# 20190213.net
KiCad netlist of a schematic drawn in EAGLE
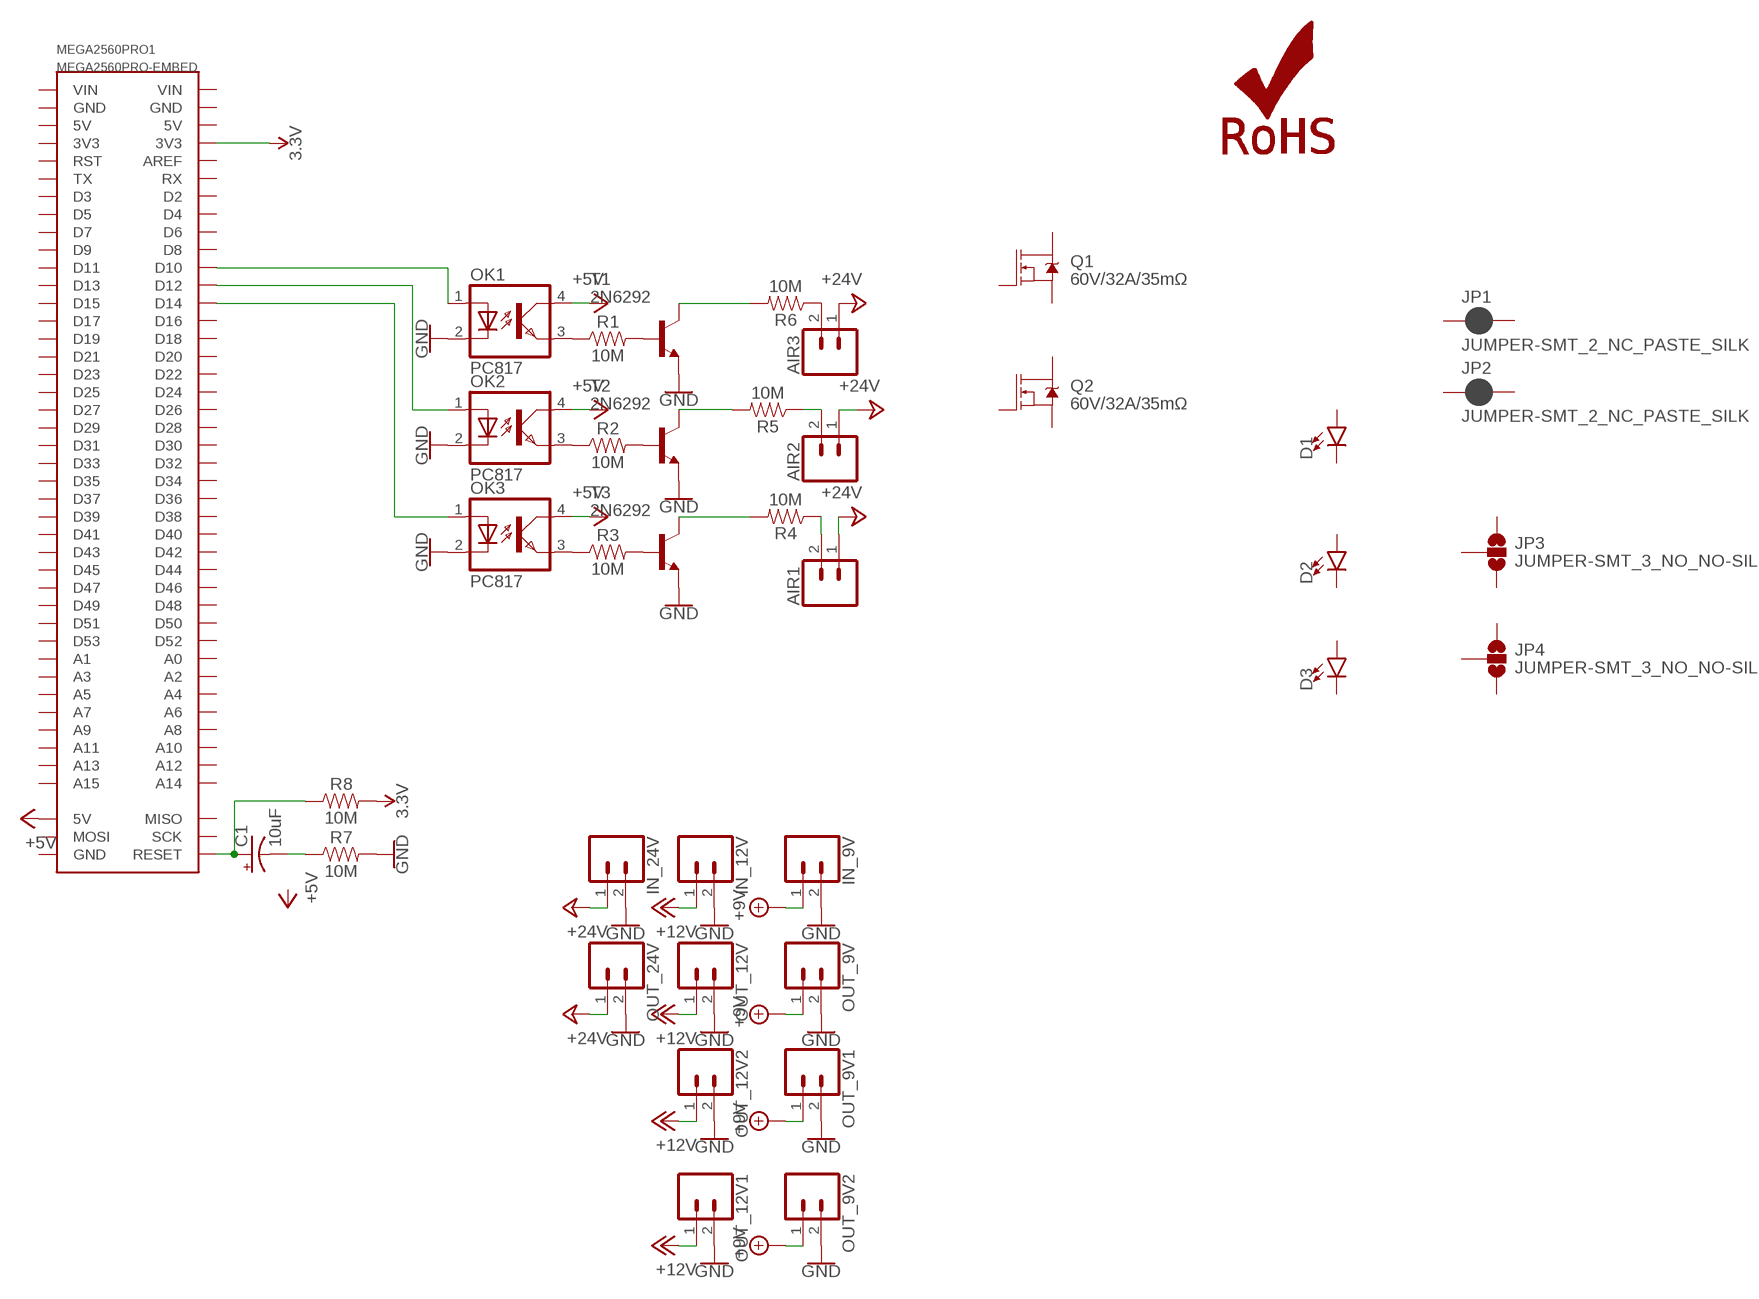
[diagram p0: schematic, sheet 1]

(export (version "E")
  (design (tool "Eeschema 10.0.6"))
  (components
    (comp (ref "AIR1")
      (value "CONN_02POLAR_LOCK")
      (footprint "eagle-import:MOLEX-1X2_LOCK")
      (libsource (lib "eagle-import") (part "CONN_02POLAR_LOCK"))
    )
    (comp (ref "AIR2")
      (value "CONN_02POLAR_LOCK")
      (footprint "eagle-import:MOLEX-1X2_LOCK")
      (libsource (lib "eagle-import") (part "CONN_02POLAR_LOCK"))
    )
    (comp (ref "AIR3")
      (value "CONN_02POLAR_LOCK")
      (footprint "eagle-import:MOLEX-1X2_LOCK")
      (libsource (lib "eagle-import") (part "CONN_02POLAR_LOCK"))
    )
    (comp (ref "C1")
      (value "10uF")
      (footprint "eagle-import:CPOL-RADIAL-2.5MM-5MM-KIT")
      (libsource (lib "eagle-import") (part "10UF-POLAR-RADIAL-2.5MM-KIT-25V-20%"))
    )
    (comp (ref "D1")
      (value "LED5MM")
      (footprint "eagle-import:LED_5MM")
      (libsource (lib "eagle-import") (part "LED5MM"))
    )
    (comp (ref "D2")
      (value "LED5MM")
      (footprint "eagle-import:LED_5MM")
      (libsource (lib "eagle-import") (part "LED5MM"))
    )
    (comp (ref "D3")
      (value "LED5MM")
      (footprint "eagle-import:LED_5MM")
      (libsource (lib "eagle-import") (part "LED5MM"))
    )
    (comp (ref "IN_9V")
      (value "CONN_02POLAR_LOCK")
      (footprint "eagle-import:MOLEX-1X2_LOCK")
      (libsource (lib "eagle-import") (part "CONN_02POLAR_LOCK"))
    )
    (comp (ref "IN_12V")
      (value "CONN_02POLAR_LOCK")
      (footprint "eagle-import:MOLEX-1X2_LOCK")
      (libsource (lib "eagle-import") (part "CONN_02POLAR_LOCK"))
    )
    (comp (ref "IN_24V")
      (value "CONN_02POLAR_LOCK")
      (footprint "eagle-import:MOLEX-1X2_LOCK")
      (libsource (lib "eagle-import") (part "CONN_02POLAR_LOCK"))
    )
    (comp (ref "JP1")
      (value "JUMPER-SMT_2_NC_PASTE_SILK")
      (footprint "eagle-import:SMT-JUMPER_2_NC_PASTE_SILK")
      (libsource (lib "eagle-import") (part "JUMPER-SMT_2_NC_PASTE_SILK"))
    )
    (comp (ref "JP2")
      (value "JUMPER-SMT_2_NC_PASTE_SILK")
      (footprint "eagle-import:SMT-JUMPER_2_NC_PASTE_SILK")
      (libsource (lib "eagle-import") (part "JUMPER-SMT_2_NC_PASTE_SILK"))
    )
    (comp (ref "JP3")
      (value "JUMPER-SMT_3_NO_NO-SILK")
      (footprint "eagle-import:SMT-JUMPER_3_NO_NO-SILK")
      (libsource (lib "eagle-import") (part "JUMPER-SMT_3_NO_NO-SILK"))
    )
    (comp (ref "JP4")
      (value "JUMPER-SMT_3_NO_NO-SILK")
      (footprint "eagle-import:SMT-JUMPER_3_NO_NO-SILK")
      (libsource (lib "eagle-import") (part "JUMPER-SMT_3_NO_NO-SILK"))
    )
    (comp (ref "LOGO1")
      (value "ROHS_LOGO")
      (footprint "eagle-import:ROHS_LOGO_0.18_IN")
      (libsource (lib "eagle-import") (part "ROHS_LOGO"))
    )
    (comp (ref "MEGA2560PRO1")
      (value "MEGA2560PRO-EMBED")
      (footprint "eagle-import:MEGA2560PRO-EMBED")
      (libsource (lib "eagle-import") (part "MEGA2560PRO-EMBED"))
    )
    (comp (ref "OK1")
      (value "PC817")
      (footprint "eagle-import:DIL04")
      (fields (field (name "MPN") "PC817X4J000F"))
      (libsource (lib "eagle-import") (part "PC817"))
    )
    (comp (ref "OK2")
      (value "PC817")
      (footprint "eagle-import:DIL04")
      (fields (field (name "MPN") "PC817X4J000F"))
      (libsource (lib "eagle-import") (part "PC817"))
    )
    (comp (ref "OK3")
      (value "PC817")
      (footprint "eagle-import:DIL04")
      (fields (field (name "MPN") "PC817X4J000F"))
      (libsource (lib "eagle-import") (part "PC817"))
    )
    (comp (ref "OUT_9V")
      (value "CONN_02POLAR_LOCK")
      (footprint "eagle-import:MOLEX-1X2_LOCK")
      (libsource (lib "eagle-import") (part "CONN_02POLAR_LOCK"))
    )
    (comp (ref "OUT_9V1")
      (value "CONN_02POLAR_LOCK")
      (footprint "eagle-import:MOLEX-1X2_LOCK")
      (libsource (lib "eagle-import") (part "CONN_02POLAR_LOCK"))
    )
    (comp (ref "OUT_9V2")
      (value "CONN_02POLAR_LOCK")
      (footprint "eagle-import:MOLEX-1X2_LOCK")
      (libsource (lib "eagle-import") (part "CONN_02POLAR_LOCK"))
    )
    (comp (ref "OUT_12V")
      (value "CONN_02POLAR_LOCK")
      (footprint "eagle-import:MOLEX-1X2_LOCK")
      (libsource (lib "eagle-import") (part "CONN_02POLAR_LOCK"))
    )
    (comp (ref "OUT_12V1")
      (value "CONN_02POLAR_LOCK")
      (footprint "eagle-import:MOLEX-1X2_LOCK")
      (libsource (lib "eagle-import") (part "CONN_02POLAR_LOCK"))
    )
    (comp (ref "OUT_12V2")
      (value "CONN_02POLAR_LOCK")
      (footprint "eagle-import:MOLEX-1X2_LOCK")
      (libsource (lib "eagle-import") (part "CONN_02POLAR_LOCK"))
    )
    (comp (ref "OUT_24V")
      (value "CONN_02POLAR_LOCK")
      (footprint "eagle-import:MOLEX-1X2_LOCK")
      (libsource (lib "eagle-import") (part "CONN_02POLAR_LOCK"))
    )
    (comp (ref "Q1")
      (value "60V/32A/35mΩ")
      (footprint "eagle-import:TO220V")
      (libsource (lib "eagle-import") (part "MOSFET-NCH-FQP30N06L"))
    )
    (comp (ref "Q2")
      (value "60V/32A/35mΩ")
      (footprint "eagle-import:TO220V")
      (libsource (lib "eagle-import") (part "MOSFET-NCH-FQP30N06L"))
    )
    (comp (ref "R1")
      (value "10M")
      (footprint "eagle-import:AXIAL-0.3")
      (libsource (lib "eagle-import") (part "10MOHM-HORIZ-1/4W-5%"))
    )
    (comp (ref "R2")
      (value "10M")
      (footprint "eagle-import:AXIAL-0.3")
      (libsource (lib "eagle-import") (part "10MOHM-HORIZ-1/4W-5%"))
    )
    (comp (ref "R3")
      (value "10M")
      (footprint "eagle-import:AXIAL-0.3")
      (libsource (lib "eagle-import") (part "10MOHM-HORIZ-1/4W-5%"))
    )
    (comp (ref "R4")
      (value "10M")
      (footprint "eagle-import:AXIAL-0.3")
      (libsource (lib "eagle-import") (part "10MOHM-HORIZ-1/4W-5%"))
    )
    (comp (ref "R5")
      (value "10M")
      (footprint "eagle-import:AXIAL-0.3")
      (libsource (lib "eagle-import") (part "10MOHM-HORIZ-1/4W-5%"))
    )
    (comp (ref "R6")
      (value "10M")
      (footprint "eagle-import:AXIAL-0.3")
      (libsource (lib "eagle-import") (part "10MOHM-HORIZ-1/4W-5%"))
    )
    (comp (ref "R7")
      (value "10M")
      (footprint "eagle-import:AXIAL-0.3")
      (libsource (lib "eagle-import") (part "10MOHM-HORIZ-1/4W-5%"))
    )
    (comp (ref "R8")
      (value "10M")
      (footprint "eagle-import:AXIAL-0.3")
      (libsource (lib "eagle-import") (part "10MOHM-HORIZ-1/4W-5%"))
    )
    (comp (ref "T1")
      (value "2N6292")
      (footprint "eagle-import:TO220")
      (libsource (lib "eagle-import") (part "2N6292"))
    )
    (comp (ref "T2")
      (value "2N6292")
      (footprint "eagle-import:TO220")
      (libsource (lib "eagle-import") (part "2N6292"))
    )
    (comp (ref "T3")
      (value "2N6292")
      (footprint "eagle-import:TO220")
      (libsource (lib "eagle-import") (part "2N6292"))
    )
  )
  (nets
    (net (code "1") (name "+5V") (class "Default")
      (node (ref "MEGA2560PRO1") (pin "5V@3") (pinfunction "5V_5V@3") (pintype "bidirectional"))
      (node (ref "OK1") (pin "4") (pinfunction "COL_4") (pintype "passive"))
      (node (ref "OK2") (pin "4") (pinfunction "COL_4") (pintype "passive"))
      (node (ref "OK3") (pin "4") (pinfunction "COL_4") (pintype "passive"))
    )
    (net (code "2") (name "+9V") (class "Default")
      (node (ref "IN_9V") (pin "1") (pinfunction "1_1") (pintype "passive"))
      (node (ref "OUT_9V") (pin "1") (pinfunction "1_1") (pintype "passive"))
      (node (ref "OUT_9V1") (pin "1") (pinfunction "1_1") (pintype "passive"))
      (node (ref "OUT_9V2") (pin "1") (pinfunction "1_1") (pintype "passive"))
    )
    (net (code "3") (name "+12V") (class "Default")
      (node (ref "IN_12V") (pin "1") (pinfunction "1_1") (pintype "passive"))
      (node (ref "OUT_12V") (pin "1") (pinfunction "1_1") (pintype "passive"))
      (node (ref "OUT_12V1") (pin "1") (pinfunction "1_1") (pintype "passive"))
      (node (ref "OUT_12V2") (pin "1") (pinfunction "1_1") (pintype "passive"))
    )
    (net (code "4") (name "+24V") (class "Default")
      (node (ref "AIR1") (pin "1") (pinfunction "1_1") (pintype "passive"))
      (node (ref "AIR2") (pin "1") (pinfunction "1_1") (pintype "passive"))
      (node (ref "AIR3") (pin "1") (pinfunction "1_1") (pintype "passive"))
      (node (ref "IN_24V") (pin "1") (pinfunction "1_1") (pintype "passive"))
      (node (ref "OUT_24V") (pin "1") (pinfunction "1_1") (pintype "passive"))
    )
    (net (code "5") (name "3.3V") (class "Default")
      (node (ref "MEGA2560PRO1") (pin "3V3@2") (pinfunction "3V3_3V3@2") (pintype "bidirectional"))
      (node (ref "R8") (pin "P$2") (pinfunction "2_P$2") (pintype "passive"))
    )
    (net (code "6") (name "GND") (class "Default")
      (node (ref "IN_12V") (pin "2") (pinfunction "2_2") (pintype "passive"))
      (node (ref "IN_24V") (pin "2") (pinfunction "2_2") (pintype "passive"))
      (node (ref "IN_9V") (pin "2") (pinfunction "2_2") (pintype "passive"))
      (node (ref "OK1") (pin "2") (pinfunction "C_2") (pintype "passive"))
      (node (ref "OK2") (pin "2") (pinfunction "C_2") (pintype "passive"))
      (node (ref "OK3") (pin "2") (pinfunction "C_2") (pintype "passive"))
      (node (ref "OUT_12V") (pin "2") (pinfunction "2_2") (pintype "passive"))
      (node (ref "OUT_12V1") (pin "2") (pinfunction "2_2") (pintype "passive"))
      (node (ref "OUT_12V2") (pin "2") (pinfunction "2_2") (pintype "passive"))
      (node (ref "OUT_24V") (pin "2") (pinfunction "2_2") (pintype "passive"))
      (node (ref "OUT_9V") (pin "2") (pinfunction "2_2") (pintype "passive"))
      (node (ref "OUT_9V1") (pin "2") (pinfunction "2_2") (pintype "passive"))
      (node (ref "OUT_9V2") (pin "2") (pinfunction "2_2") (pintype "passive"))
      (node (ref "R7") (pin "P$2") (pinfunction "2_P$2") (pintype "passive"))
      (node (ref "T1") (pin "3") (pinfunction "E_3") (pintype "passive"))
      (node (ref "T2") (pin "3") (pinfunction "E_3") (pintype "passive"))
      (node (ref "T3") (pin "3") (pinfunction "E_3") (pintype "passive"))
    )
    (net (code "7") (name "Net-(C1-+)") (class "Default")
      (node (ref "C1") (pin "1") (pinfunction "+_1") (pintype "passive"))
      (node (ref "MEGA2560PRO1") (pin "RESET") (pinfunction "RESET_RESET") (pintype "bidirectional"))
      (node (ref "R8") (pin "P$1") (pinfunction "1_P$1") (pintype "passive"))
    )
    (net (code "8") (name "Net-(C1--)") (class "Default")
      (node (ref "C1") (pin "2") (pinfunction "-_2") (pintype "passive"))
      (node (ref "R7") (pin "P$1") (pinfunction "1_P$1") (pintype "passive"))
    )
    (net (code "9") (name "Net-(OK1-A)") (class "Default")
      (node (ref "MEGA2560PRO1") (pin "D10") (pinfunction "D10_D10") (pintype "bidirectional"))
      (node (ref "OK1") (pin "1") (pinfunction "A_1") (pintype "passive"))
    )
    (net (code "10") (name "Net-(OK1-EMIT)") (class "Default")
      (node (ref "OK1") (pin "3") (pinfunction "EMIT_3") (pintype "passive"))
      (node (ref "R1") (pin "P$1") (pinfunction "1_P$1") (pintype "passive"))
    )
    (net (code "11") (name "Net-(OK2-A)") (class "Default")
      (node (ref "MEGA2560PRO1") (pin "D12") (pinfunction "D12_D12") (pintype "bidirectional"))
      (node (ref "OK2") (pin "1") (pinfunction "A_1") (pintype "passive"))
    )
    (net (code "12") (name "Net-(OK2-EMIT)") (class "Default")
      (node (ref "OK2") (pin "3") (pinfunction "EMIT_3") (pintype "passive"))
      (node (ref "R2") (pin "P$1") (pinfunction "1_P$1") (pintype "passive"))
    )
    (net (code "13") (name "Net-(OK3-A)") (class "Default")
      (node (ref "MEGA2560PRO1") (pin "D14") (pinfunction "D14_D14") (pintype "bidirectional"))
      (node (ref "OK3") (pin "1") (pinfunction "A_1") (pintype "passive"))
    )
    (net (code "14") (name "Net-(OK3-EMIT)") (class "Default")
      (node (ref "OK3") (pin "3") (pinfunction "EMIT_3") (pintype "passive"))
      (node (ref "R3") (pin "P$1") (pinfunction "1_P$1") (pintype "passive"))
    )
    (net (code "15") (name "Net-(R1-2)") (class "Default")
      (node (ref "R1") (pin "P$2") (pinfunction "2_P$2") (pintype "passive"))
      (node (ref "T1") (pin "1") (pinfunction "B_1") (pintype "passive"))
    )
    (net (code "16") (name "Net-(R2-2)") (class "Default")
      (node (ref "R2") (pin "P$2") (pinfunction "2_P$2") (pintype "passive"))
      (node (ref "T2") (pin "1") (pinfunction "B_1") (pintype "passive"))
    )
    (net (code "17") (name "Net-(R3-2)") (class "Default")
      (node (ref "R3") (pin "P$2") (pinfunction "2_P$2") (pintype "passive"))
      (node (ref "T3") (pin "1") (pinfunction "B_1") (pintype "passive"))
    )
    (net (code "18") (name "Net-(R4-1)") (class "Default")
      (node (ref "AIR1") (pin "2") (pinfunction "2_2") (pintype "passive"))
      (node (ref "R4") (pin "P$1") (pinfunction "1_P$1") (pintype "passive"))
    )
    (net (code "19") (name "Net-(R4-2)") (class "Default")
      (node (ref "R4") (pin "P$2") (pinfunction "2_P$2") (pintype "passive"))
      (node (ref "T3") (pin "2") (pinfunction "C_2") (pintype "passive"))
    )
    (net (code "20") (name "Net-(R5-1)") (class "Default")
      (node (ref "AIR2") (pin "2") (pinfunction "2_2") (pintype "passive"))
      (node (ref "R5") (pin "P$1") (pinfunction "1_P$1") (pintype "passive"))
    )
    (net (code "21") (name "Net-(R5-2)") (class "Default")
      (node (ref "R5") (pin "P$2") (pinfunction "2_P$2") (pintype "passive"))
      (node (ref "T2") (pin "2") (pinfunction "C_2") (pintype "passive"))
    )
    (net (code "22") (name "Net-(R6-1)") (class "Default")
      (node (ref "AIR3") (pin "2") (pinfunction "2_2") (pintype "passive"))
      (node (ref "R6") (pin "P$1") (pinfunction "1_P$1") (pintype "passive"))
    )
    (net (code "23") (name "Net-(R6-2)") (class "Default")
      (node (ref "R6") (pin "P$2") (pinfunction "2_P$2") (pintype "passive"))
      (node (ref "T1") (pin "2") (pinfunction "C_2") (pintype "passive"))
    )
    (net (code "24") (name "unconnected-(D1-C-PadK)") (class "Default")
      (node (ref "D1") (pin "K") (pinfunction "C_K") (pintype "passive"))
    )
    (net (code "25") (name "unconnected-(D1-PadA)") (class "Default")
      (node (ref "D1") (pin "A") (pinfunction "A_A") (pintype "passive"))
    )
    (net (code "26") (name "unconnected-(D2-C-PadK)") (class "Default")
      (node (ref "D2") (pin "K") (pinfunction "C_K") (pintype "passive"))
    )
    (net (code "27") (name "unconnected-(D2-PadA)") (class "Default")
      (node (ref "D2") (pin "A") (pinfunction "A_A") (pintype "passive"))
    )
    (net (code "28") (name "unconnected-(D3-C-PadK)") (class "Default")
      (node (ref "D3") (pin "K") (pinfunction "C_K") (pintype "passive"))
    )
    (net (code "29") (name "unconnected-(D3-PadA)") (class "Default")
      (node (ref "D3") (pin "A") (pinfunction "A_A") (pintype "passive"))
    )
    (net (code "30") (name "unconnected-(JP1-Pad1)") (class "Default")
      (node (ref "JP1") (pin "1") (pinfunction "1_1") (pintype "passive"))
    )
    (net (code "31") (name "unconnected-(JP1-Pad2)") (class "Default")
      (node (ref "JP1") (pin "2") (pinfunction "2_2") (pintype "passive"))
    )
    (net (code "32") (name "unconnected-(JP2-Pad1)") (class "Default")
      (node (ref "JP2") (pin "1") (pinfunction "1_1") (pintype "passive"))
    )
    (net (code "33") (name "unconnected-(JP2-Pad2)") (class "Default")
      (node (ref "JP2") (pin "2") (pinfunction "2_2") (pintype "passive"))
    )
    (net (code "34") (name "unconnected-(JP3-Pad1)") (class "Default")
      (node (ref "JP3") (pin "1") (pinfunction "1_1") (pintype "passive"))
    )
    (net (code "35") (name "unconnected-(JP3-Pad2)") (class "Default")
      (node (ref "JP3") (pin "2") (pinfunction "2_2") (pintype "passive"))
    )
    (net (code "36") (name "unconnected-(JP3-Pad3)") (class "Default")
      (node (ref "JP3") (pin "3") (pinfunction "3_3") (pintype "passive"))
    )
    (net (code "37") (name "unconnected-(JP4-Pad1)") (class "Default")
      (node (ref "JP4") (pin "1") (pinfunction "1_1") (pintype "passive"))
    )
    (net (code "38") (name "unconnected-(JP4-Pad2)") (class "Default")
      (node (ref "JP4") (pin "2") (pinfunction "2_2") (pintype "passive"))
    )
    (net (code "39") (name "unconnected-(JP4-Pad3)") (class "Default")
      (node (ref "JP4") (pin "3") (pinfunction "3_3") (pintype "passive"))
    )
    (net (code "40") (name "unconnected-(MEGA2560PRO1-3V3-Pad3V3@1)") (class "Default")
      (node (ref "MEGA2560PRO1") (pin "3V3@1") (pinfunction "3V3_3V3@1") (pintype "bidirectional"))
    )
    (net (code "41") (name "unconnected-(MEGA2560PRO1-5V-Pad5V@1)") (class "Default")
      (node (ref "MEGA2560PRO1") (pin "5V@1") (pinfunction "5V_5V@1") (pintype "bidirectional"))
    )
    (net (code "42") (name "unconnected-(MEGA2560PRO1-5V-Pad5V@2)") (class "Default")
      (node (ref "MEGA2560PRO1") (pin "5V@2") (pinfunction "5V_5V@2") (pintype "bidirectional"))
    )
    (net (code "43") (name "unconnected-(MEGA2560PRO1-GND-PadGND@1)") (class "Default")
      (node (ref "MEGA2560PRO1") (pin "GND@1") (pinfunction "GND_GND@1") (pintype "bidirectional"))
    )
    (net (code "44") (name "unconnected-(MEGA2560PRO1-GND-PadGND@2)") (class "Default")
      (node (ref "MEGA2560PRO1") (pin "GND@2") (pinfunction "GND_GND@2") (pintype "bidirectional"))
    )
    (net (code "45") (name "unconnected-(MEGA2560PRO1-GND-PadGND@3)") (class "Default")
      (node (ref "MEGA2560PRO1") (pin "GND@3") (pinfunction "GND_GND@3") (pintype "bidirectional"))
    )
    (net (code "46") (name "unconnected-(MEGA2560PRO1-PadA0)") (class "Default")
      (node (ref "MEGA2560PRO1") (pin "A0") (pinfunction "A0_A0") (pintype "bidirectional"))
    )
    (net (code "47") (name "unconnected-(MEGA2560PRO1-PadA1)") (class "Default")
      (node (ref "MEGA2560PRO1") (pin "A1") (pinfunction "A1_A1") (pintype "bidirectional"))
    )
    (net (code "48") (name "unconnected-(MEGA2560PRO1-PadA2)") (class "Default")
      (node (ref "MEGA2560PRO1") (pin "A2") (pinfunction "A2_A2") (pintype "bidirectional"))
    )
    (net (code "49") (name "unconnected-(MEGA2560PRO1-PadA3)") (class "Default")
      (node (ref "MEGA2560PRO1") (pin "A3") (pinfunction "A3_A3") (pintype "bidirectional"))
    )
    (net (code "50") (name "unconnected-(MEGA2560PRO1-PadA4)") (class "Default")
      (node (ref "MEGA2560PRO1") (pin "A4") (pinfunction "A4_A4") (pintype "bidirectional"))
    )
    (net (code "51") (name "unconnected-(MEGA2560PRO1-PadA5)") (class "Default")
      (node (ref "MEGA2560PRO1") (pin "A5") (pinfunction "A5_A5") (pintype "bidirectional"))
    )
    (net (code "52") (name "unconnected-(MEGA2560PRO1-PadA6)") (class "Default")
      (node (ref "MEGA2560PRO1") (pin "A6") (pinfunction "A6_A6") (pintype "bidirectional"))
    )
    (net (code "53") (name "unconnected-(MEGA2560PRO1-PadA7)") (class "Default")
      (node (ref "MEGA2560PRO1") (pin "A7") (pinfunction "A7_A7") (pintype "bidirectional"))
    )
    (net (code "54") (name "unconnected-(MEGA2560PRO1-PadA8)") (class "Default")
      (node (ref "MEGA2560PRO1") (pin "A8") (pinfunction "A8_A8") (pintype "bidirectional"))
    )
    (net (code "55") (name "unconnected-(MEGA2560PRO1-PadA9)") (class "Default")
      (node (ref "MEGA2560PRO1") (pin "A9") (pinfunction "A9_A9") (pintype "bidirectional"))
    )
    (net (code "56") (name "unconnected-(MEGA2560PRO1-PadA10)") (class "Default")
      (node (ref "MEGA2560PRO1") (pin "A10") (pinfunction "A10_A10") (pintype "bidirectional"))
    )
    (net (code "57") (name "unconnected-(MEGA2560PRO1-PadA11)") (class "Default")
      (node (ref "MEGA2560PRO1") (pin "A11") (pinfunction "A11_A11") (pintype "bidirectional"))
    )
    (net (code "58") (name "unconnected-(MEGA2560PRO1-PadA12)") (class "Default")
      (node (ref "MEGA2560PRO1") (pin "A12") (pinfunction "A12_A12") (pintype "bidirectional"))
    )
    (net (code "59") (name "unconnected-(MEGA2560PRO1-PadA13)") (class "Default")
      (node (ref "MEGA2560PRO1") (pin "A13") (pinfunction "A13_A13") (pintype "bidirectional"))
    )
    (net (code "60") (name "unconnected-(MEGA2560PRO1-PadA14)") (class "Default")
      (node (ref "MEGA2560PRO1") (pin "A14") (pinfunction "A14_A14") (pintype "bidirectional"))
    )
    (net (code "61") (name "unconnected-(MEGA2560PRO1-PadA15)") (class "Default")
      (node (ref "MEGA2560PRO1") (pin "A15") (pinfunction "A15_A15") (pintype "bidirectional"))
    )
    (net (code "62") (name "unconnected-(MEGA2560PRO1-PadAREF)") (class "Default")
      (node (ref "MEGA2560PRO1") (pin "AREF") (pinfunction "AREF_AREF") (pintype "bidirectional"))
    )
    (net (code "63") (name "unconnected-(MEGA2560PRO1-PadD2)") (class "Default")
      (node (ref "MEGA2560PRO1") (pin "D2") (pinfunction "D2_D2") (pintype "bidirectional"))
    )
    (net (code "64") (name "unconnected-(MEGA2560PRO1-PadD3)") (class "Default")
      (node (ref "MEGA2560PRO1") (pin "D3") (pinfunction "D3_D3") (pintype "bidirectional"))
    )
    (net (code "65") (name "unconnected-(MEGA2560PRO1-PadD4)") (class "Default")
      (node (ref "MEGA2560PRO1") (pin "D4") (pinfunction "D4_D4") (pintype "bidirectional"))
    )
    (net (code "66") (name "unconnected-(MEGA2560PRO1-PadD5)") (class "Default")
      (node (ref "MEGA2560PRO1") (pin "D5") (pinfunction "D5_D5") (pintype "bidirectional"))
    )
    (net (code "67") (name "unconnected-(MEGA2560PRO1-PadD6)") (class "Default")
      (node (ref "MEGA2560PRO1") (pin "D6") (pinfunction "D6_D6") (pintype "bidirectional"))
    )
    (net (code "68") (name "unconnected-(MEGA2560PRO1-PadD7)") (class "Default")
      (node (ref "MEGA2560PRO1") (pin "D7") (pinfunction "D7_D7") (pintype "bidirectional"))
    )
    (net (code "69") (name "unconnected-(MEGA2560PRO1-PadD8)") (class "Default")
      (node (ref "MEGA2560PRO1") (pin "D8") (pinfunction "D8_D8") (pintype "bidirectional"))
    )
    (net (code "70") (name "unconnected-(MEGA2560PRO1-PadD9)") (class "Default")
      (node (ref "MEGA2560PRO1") (pin "D9") (pinfunction "D9_D9") (pintype "bidirectional"))
    )
    (net (code "71") (name "unconnected-(MEGA2560PRO1-PadD11)") (class "Default")
      (node (ref "MEGA2560PRO1") (pin "D11") (pinfunction "D11_D11") (pintype "bidirectional"))
    )
    (net (code "72") (name "unconnected-(MEGA2560PRO1-PadD13)") (class "Default")
      (node (ref "MEGA2560PRO1") (pin "D13") (pinfunction "D13_D13") (pintype "bidirectional"))
    )
    (net (code "73") (name "unconnected-(MEGA2560PRO1-PadD15)") (class "Default")
      (node (ref "MEGA2560PRO1") (pin "D15") (pinfunction "D15_D15") (pintype "bidirectional"))
    )
    (net (code "74") (name "unconnected-(MEGA2560PRO1-PadD16)") (class "Default")
      (node (ref "MEGA2560PRO1") (pin "D16") (pinfunction "D16_D16") (pintype "bidirectional"))
    )
    (net (code "75") (name "unconnected-(MEGA2560PRO1-PadD17)") (class "Default")
      (node (ref "MEGA2560PRO1") (pin "D17") (pinfunction "D17_D17") (pintype "bidirectional"))
    )
    (net (code "76") (name "unconnected-(MEGA2560PRO1-PadD18)") (class "Default")
      (node (ref "MEGA2560PRO1") (pin "D18") (pinfunction "D18_D18") (pintype "bidirectional"))
    )
    (net (code "77") (name "unconnected-(MEGA2560PRO1-PadD19)") (class "Default")
      (node (ref "MEGA2560PRO1") (pin "D19") (pinfunction "D19_D19") (pintype "bidirectional"))
    )
    (net (code "78") (name "unconnected-(MEGA2560PRO1-PadD20)") (class "Default")
      (node (ref "MEGA2560PRO1") (pin "D20") (pinfunction "D20_D20") (pintype "bidirectional"))
    )
    (net (code "79") (name "unconnected-(MEGA2560PRO1-PadD21)") (class "Default")
      (node (ref "MEGA2560PRO1") (pin "D21") (pinfunction "D21_D21") (pintype "bidirectional"))
    )
    (net (code "80") (name "unconnected-(MEGA2560PRO1-PadD22)") (class "Default")
      (node (ref "MEGA2560PRO1") (pin "D22") (pinfunction "D22_D22") (pintype "bidirectional"))
    )
    (net (code "81") (name "unconnected-(MEGA2560PRO1-PadD23)") (class "Default")
      (node (ref "MEGA2560PRO1") (pin "D23") (pinfunction "D23_D23") (pintype "bidirectional"))
    )
    (net (code "82") (name "unconnected-(MEGA2560PRO1-PadD24)") (class "Default")
      (node (ref "MEGA2560PRO1") (pin "D24") (pinfunction "D24_D24") (pintype "bidirectional"))
    )
    (net (code "83") (name "unconnected-(MEGA2560PRO1-PadD25)") (class "Default")
      (node (ref "MEGA2560PRO1") (pin "D25") (pinfunction "D25_D25") (pintype "bidirectional"))
    )
    (net (code "84") (name "unconnected-(MEGA2560PRO1-PadD26)") (class "Default")
      (node (ref "MEGA2560PRO1") (pin "D26") (pinfunction "D26_D26") (pintype "bidirectional"))
    )
    (net (code "85") (name "unconnected-(MEGA2560PRO1-PadD27)") (class "Default")
      (node (ref "MEGA2560PRO1") (pin "D27") (pinfunction "D27_D27") (pintype "bidirectional"))
    )
    (net (code "86") (name "unconnected-(MEGA2560PRO1-PadD28)") (class "Default")
      (node (ref "MEGA2560PRO1") (pin "D28") (pinfunction "D28_D28") (pintype "bidirectional"))
    )
    (net (code "87") (name "unconnected-(MEGA2560PRO1-PadD29)") (class "Default")
      (node (ref "MEGA2560PRO1") (pin "D29") (pinfunction "D29_D29") (pintype "bidirectional"))
    )
    (net (code "88") (name "unconnected-(MEGA2560PRO1-PadD30)") (class "Default")
      (node (ref "MEGA2560PRO1") (pin "D30") (pinfunction "D30_D30") (pintype "bidirectional"))
    )
    (net (code "89") (name "unconnected-(MEGA2560PRO1-PadD31)") (class "Default")
      (node (ref "MEGA2560PRO1") (pin "D31") (pinfunction "D31_D31") (pintype "bidirectional"))
    )
    (net (code "90") (name "unconnected-(MEGA2560PRO1-PadD32)") (class "Default")
      (node (ref "MEGA2560PRO1") (pin "D32") (pinfunction "D32_D32") (pintype "bidirectional"))
    )
    (net (code "91") (name "unconnected-(MEGA2560PRO1-PadD33)") (class "Default")
      (node (ref "MEGA2560PRO1") (pin "D33") (pinfunction "D33_D33") (pintype "bidirectional"))
    )
    (net (code "92") (name "unconnected-(MEGA2560PRO1-PadD34)") (class "Default")
      (node (ref "MEGA2560PRO1") (pin "D34") (pinfunction "D34_D34") (pintype "bidirectional"))
    )
    (net (code "93") (name "unconnected-(MEGA2560PRO1-PadD35)") (class "Default")
      (node (ref "MEGA2560PRO1") (pin "D35") (pinfunction "D35_D35") (pintype "bidirectional"))
    )
    (net (code "94") (name "unconnected-(MEGA2560PRO1-PadD36)") (class "Default")
      (node (ref "MEGA2560PRO1") (pin "D36") (pinfunction "D36_D36") (pintype "bidirectional"))
    )
    (net (code "95") (name "unconnected-(MEGA2560PRO1-PadD37)") (class "Default")
      (node (ref "MEGA2560PRO1") (pin "D37") (pinfunction "D37_D37") (pintype "bidirectional"))
    )
    (net (code "96") (name "unconnected-(MEGA2560PRO1-PadD38)") (class "Default")
      (node (ref "MEGA2560PRO1") (pin "D38") (pinfunction "D38_D38") (pintype "bidirectional"))
    )
    (net (code "97") (name "unconnected-(MEGA2560PRO1-PadD39)") (class "Default")
      (node (ref "MEGA2560PRO1") (pin "D39") (pinfunction "D39_D39") (pintype "bidirectional"))
    )
    (net (code "98") (name "unconnected-(MEGA2560PRO1-PadD40)") (class "Default")
      (node (ref "MEGA2560PRO1") (pin "D40") (pinfunction "D40_D40") (pintype "bidirectional"))
    )
    (net (code "99") (name "unconnected-(MEGA2560PRO1-PadD41)") (class "Default")
      (node (ref "MEGA2560PRO1") (pin "D41") (pinfunction "D41_D41") (pintype "bidirectional"))
    )
    (net (code "100") (name "unconnected-(MEGA2560PRO1-PadD42)") (class "Default")
      (node (ref "MEGA2560PRO1") (pin "D42") (pinfunction "D42_D42") (pintype "bidirectional"))
    )
    (net (code "101") (name "unconnected-(MEGA2560PRO1-PadD43)") (class "Default")
      (node (ref "MEGA2560PRO1") (pin "D43") (pinfunction "D43_D43") (pintype "bidirectional"))
    )
    (net (code "102") (name "unconnected-(MEGA2560PRO1-PadD44)") (class "Default")
      (node (ref "MEGA2560PRO1") (pin "D44") (pinfunction "D44_D44") (pintype "bidirectional"))
    )
    (net (code "103") (name "unconnected-(MEGA2560PRO1-PadD45)") (class "Default")
      (node (ref "MEGA2560PRO1") (pin "D45") (pinfunction "D45_D45") (pintype "bidirectional"))
    )
    (net (code "104") (name "unconnected-(MEGA2560PRO1-PadD46)") (class "Default")
      (node (ref "MEGA2560PRO1") (pin "D46") (pinfunction "D46_D46") (pintype "bidirectional"))
    )
    (net (code "105") (name "unconnected-(MEGA2560PRO1-PadD47)") (class "Default")
      (node (ref "MEGA2560PRO1") (pin "D47") (pinfunction "D47_D47") (pintype "bidirectional"))
    )
    (net (code "106") (name "unconnected-(MEGA2560PRO1-PadD48)") (class "Default")
      (node (ref "MEGA2560PRO1") (pin "D48") (pinfunction "D48_D48") (pintype "bidirectional"))
    )
    (net (code "107") (name "unconnected-(MEGA2560PRO1-PadD49)") (class "Default")
      (node (ref "MEGA2560PRO1") (pin "D49") (pinfunction "D49_D49") (pintype "bidirectional"))
    )
    (net (code "108") (name "unconnected-(MEGA2560PRO1-PadD50)") (class "Default")
      (node (ref "MEGA2560PRO1") (pin "D50") (pinfunction "D50_D50") (pintype "bidirectional"))
    )
    (net (code "109") (name "unconnected-(MEGA2560PRO1-PadD51)") (class "Default")
      (node (ref "MEGA2560PRO1") (pin "D51") (pinfunction "D51_D51") (pintype "bidirectional"))
    )
    (net (code "110") (name "unconnected-(MEGA2560PRO1-PadD52)") (class "Default")
      (node (ref "MEGA2560PRO1") (pin "D52") (pinfunction "D52_D52") (pintype "bidirectional"))
    )
    (net (code "111") (name "unconnected-(MEGA2560PRO1-PadD53)") (class "Default")
      (node (ref "MEGA2560PRO1") (pin "D53") (pinfunction "D53_D53") (pintype "bidirectional"))
    )
    (net (code "112") (name "unconnected-(MEGA2560PRO1-PadMISO)") (class "Default")
      (node (ref "MEGA2560PRO1") (pin "MISO") (pinfunction "MISO_MISO") (pintype "bidirectional"))
    )
    (net (code "113") (name "unconnected-(MEGA2560PRO1-PadMOSI)") (class "Default")
      (node (ref "MEGA2560PRO1") (pin "MOSI") (pinfunction "MOSI_MOSI") (pintype "bidirectional"))
    )
    (net (code "114") (name "unconnected-(MEGA2560PRO1-PadRST)") (class "Default")
      (node (ref "MEGA2560PRO1") (pin "RST") (pinfunction "RST_RST") (pintype "bidirectional"))
    )
    (net (code "115") (name "unconnected-(MEGA2560PRO1-PadRX)") (class "Default")
      (node (ref "MEGA2560PRO1") (pin "RX") (pinfunction "RX_RX") (pintype "bidirectional"))
    )
    (net (code "116") (name "unconnected-(MEGA2560PRO1-PadSCK)") (class "Default")
      (node (ref "MEGA2560PRO1") (pin "SCK") (pinfunction "SCK_SCK") (pintype "bidirectional"))
    )
    (net (code "117") (name "unconnected-(MEGA2560PRO1-PadTX)") (class "Default")
      (node (ref "MEGA2560PRO1") (pin "TX") (pinfunction "TX_TX") (pintype "bidirectional"))
    )
    (net (code "118") (name "unconnected-(MEGA2560PRO1-VIN-PadVIN@1)") (class "Default")
      (node (ref "MEGA2560PRO1") (pin "VIN@1") (pinfunction "VIN_VIN@1") (pintype "bidirectional"))
    )
    (net (code "119") (name "unconnected-(MEGA2560PRO1-VIN-PadVIN@2)") (class "Default")
      (node (ref "MEGA2560PRO1") (pin "VIN@2") (pinfunction "VIN_VIN@2") (pintype "bidirectional"))
    )
    (net (code "120") (name "unconnected-(Q1-D-Pad2)") (class "Default")
      (node (ref "Q1") (pin "2") (pinfunction "D_2") (pintype "bidirectional"))
    )
    (net (code "121") (name "unconnected-(Q1-G-Pad1)") (class "Default")
      (node (ref "Q1") (pin "1") (pinfunction "G_1") (pintype "bidirectional"))
    )
    (net (code "122") (name "unconnected-(Q1-S-Pad3)") (class "Default")
      (node (ref "Q1") (pin "3") (pinfunction "S_3") (pintype "bidirectional"))
    )
    (net (code "123") (name "unconnected-(Q2-D-Pad2)") (class "Default")
      (node (ref "Q2") (pin "2") (pinfunction "D_2") (pintype "bidirectional"))
    )
    (net (code "124") (name "unconnected-(Q2-G-Pad1)") (class "Default")
      (node (ref "Q2") (pin "1") (pinfunction "G_1") (pintype "bidirectional"))
    )
    (net (code "125") (name "unconnected-(Q2-S-Pad3)") (class "Default")
      (node (ref "Q2") (pin "3") (pinfunction "S_3") (pintype "bidirectional"))
    )
  )
)
